# ISL6236A.net
KiCad netlist of a schematic drawn in Altium Designer
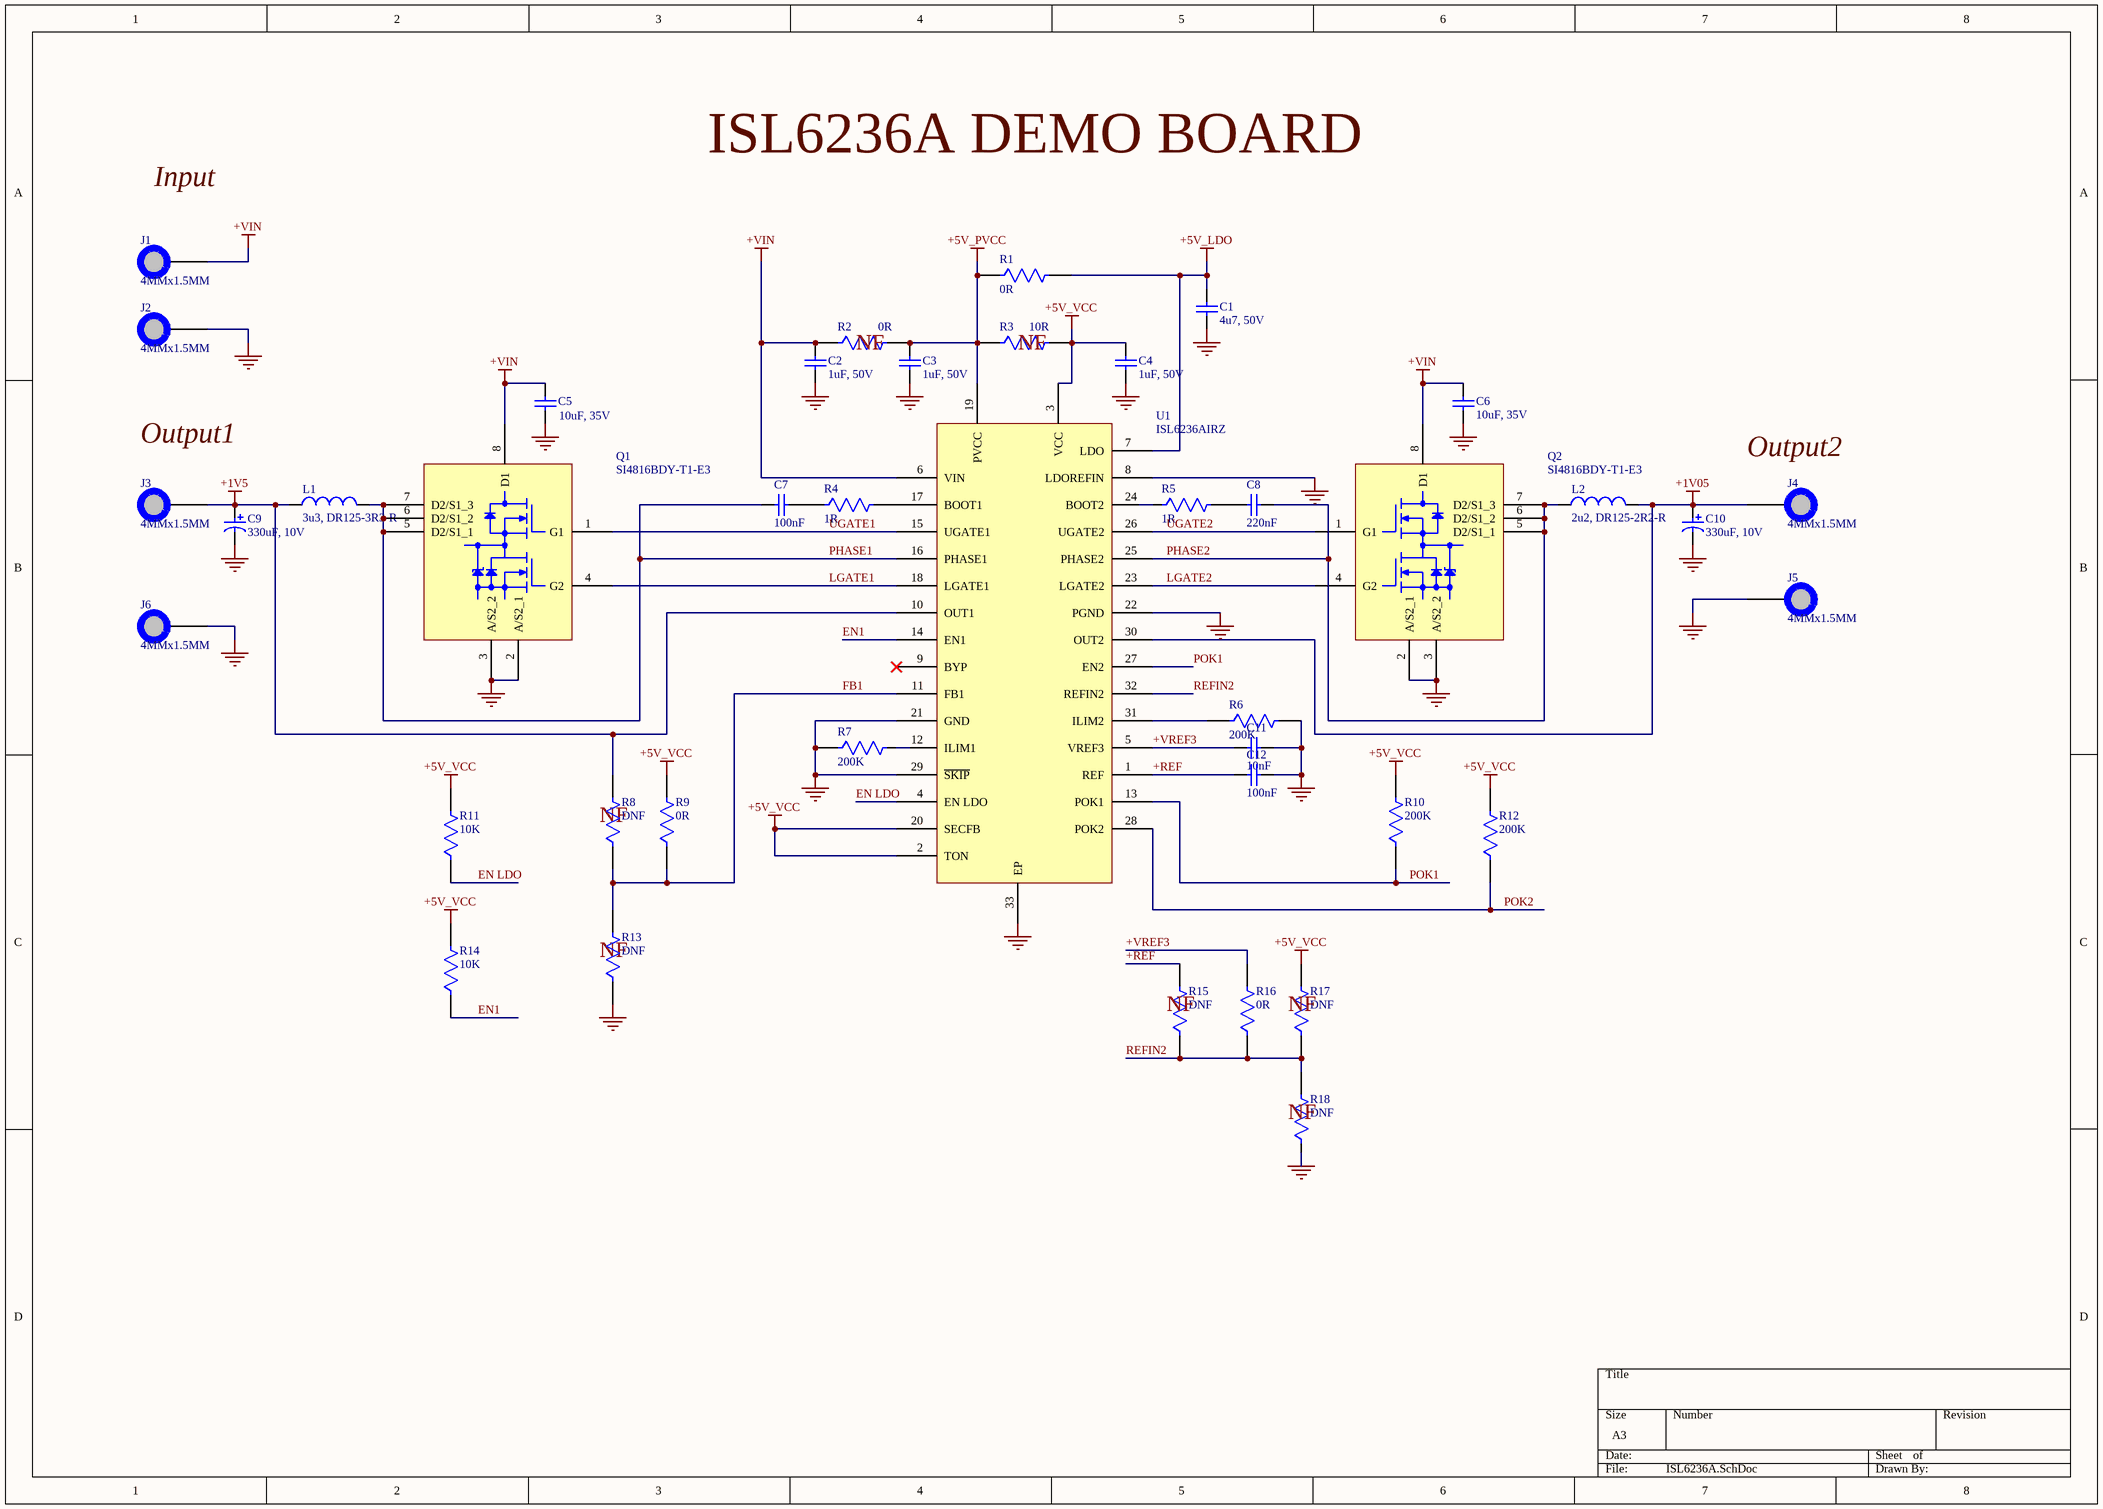
[diagram p0: ISL6236A.SchDoc]

(export (version "E")
  (design (tool "Eeschema 10.0.6"))
  (components
    (comp (ref "C1")
      (value "4u7, 50V")
      (footprint "C1206")
      (description "C Series 1206 4.7 uF 50 V ±10 % Tolerance X5R SMT Multilayer Ceramic Capacitor")
      (fields
        (field (name "MANUFACTURER") "TDK")
        (field (name "MANUFACTURER PART NUMBER") "C3216X5R1H475K160AB")
      )
      (libsource (lib "ISL6236A") (part "C3216X5R1H475K160AB"))
    )
    (comp (ref "C2")
      (value "1uF, 50V")
      (footprint "C0805")
      (description "0805 C 1uF Ceramic Multilayer Capacitor; 50 V; +125degC; X7R Dielectric; +/-10%")
      (fields (field (name "MANUFACTURER") "KEMET") (field (name "TOLERANCE") "10%"))
      (libsource (lib "ISL6236A") (part "C0805C105K5RACTU"))
    )
    (comp (ref "C3")
      (value "1uF, 50V")
      (footprint "C0805")
      (description "0805 C 1uF Ceramic Multilayer Capacitor; 50 V; +125degC; X7R Dielectric; +/-10%")
      (fields (field (name "MANUFACTURER") "KEMET") (field (name "TOLERANCE") "10%"))
      (libsource (lib "ISL6236A") (part "C0805C105K5RACTU"))
    )
    (comp (ref "C4")
      (value "1uF, 50V")
      (footprint "C0805")
      (description "0805 C 1uF Ceramic Multilayer Capacitor; 50 V; +125degC; X7R Dielectric; +/-10%")
      (fields (field (name "MANUFACTURER") "KEMET") (field (name "TOLERANCE") "10%"))
      (libsource (lib "ISL6236A") (part "C0805C105K5RACTU"))
    )
    (comp (ref "C5")
      (value "10uF, 35V")
      (footprint "C1210")
      (fields
        (field (name "MANUFACTURER") "KEMET")
        (field (name "MANUFACTURER PART NUMBER") "C1210C106K6PACTU")
        (field (name "VOLTAGE") "35V")
      )
      (libsource (lib "ISL6236A") (part "C1210C106K6PACTU"))
    )
    (comp (ref "C6")
      (value "10uF, 35V")
      (footprint "C1210")
      (fields
        (field (name "MANUFACTURER") "KEMET")
        (field (name "MANUFACTURER PART NUMBER") "C1210C106K6PACTU")
        (field (name "VOLTAGE") "35V")
      )
      (libsource (lib "ISL6236A") (part "C1210C106K6PACTU"))
    )
    (comp (ref "C7")
      (value "100nF")
      (footprint "C0805")
      (description "Cap Ceramic 0.1uF 50V X7R 10% SMD 2.0 x 1.2 mm 125 C Paper T/R")
      (fields
        (field (name "MANUFACTURER") "KEMET")
        (field (name "MANUFACTURER PART NUMBER") "C0805C104K5RACTU")
      )
      (libsource (lib "ISL6236A") (part "C0805C104K5RACTU"))
    )
    (comp (ref "C8")
      (value "220nF")
      (footprint "C0805")
      (description "CAP CER 0.22UF 50V X7R 0805")
      (fields
        (field (name "MANUFACTURER") "KEMET")
        (field (name "MANUFACTURER PART NUMBER") "C0805C224K5RACTU")
      )
      (libsource (lib "ISL6236A") (part "C0805C224K5RACTU"))
    )
    (comp (ref "C9")
      (value "330uF, 10V")
      (footprint "7343-43")
      (description "Cap Tant Organic 330uF 10VDC X CASE 20% (7.3 X 4.3 X 4mm) SMD 7343-43 0.004 Ohm 125C T/R")
      (fields
        (field (name "MANUFACTURER") "KEMET")
        (field (name "MANUFACTURER PART NUMBER") "T530X337M010ATE004")
      )
      (libsource (lib "ISL6236A") (part "T530X337M010ATE004"))
    )
    (comp (ref "C10")
      (value "330uF, 10V")
      (footprint "7343-43")
      (description "Cap Tant Organic 330uF 10VDC X CASE 20% (7.3 X 4.3 X 4mm) SMD 7343-43 0.004 Ohm 125C T/R")
      (fields
        (field (name "MANUFACTURER") "KEMET")
        (field (name "MANUFACTURER PART NUMBER") "T530X337M010ATE004")
      )
      (libsource (lib "ISL6236A") (part "T530X337M010ATE004"))
    )
    (comp (ref "C11")
      (value "10nF")
      (footprint "C0805")
      (fields
        (field (name "MANUFACTURER") "KEMET")
        (field (name "MANUFACTURER PART NUMBER") "C0805F103K5RACTU")
        (field (name "TOLERANCE") "10%")
      )
      (libsource (lib "ISL6236A") (part "C0805F103K5RACTU"))
    )
    (comp (ref "C12")
      (value "100nF")
      (footprint "C0805")
      (description "Cap Ceramic 0.1uF 50V X7R 10% SMD 2.0 x 1.2 mm 125 C Paper T/R")
      (fields
        (field (name "MANUFACTURER") "KEMET")
        (field (name "MANUFACTURER PART NUMBER") "C0805C104K5RACTU")
      )
      (libsource (lib "ISL6236A") (part "C0805C104K5RACTU"))
    )
    (comp (ref "J1")
      (value "4MMx1.5MM")
      (footprint "PAD_WITH_HOLE_4MMx1MM5")
      (description "Pad with a hole 4mm x 1.5mm")
      (libsource (lib "ISL6236A") (part "PAD_WITH_HOLE_4MMx1MM5"))
    )
    (comp (ref "J2")
      (value "4MMx1.5MM")
      (footprint "PAD_WITH_HOLE_4MMx1MM5")
      (description "Pad with a hole 4mm x 1.5mm")
      (libsource (lib "ISL6236A") (part "PAD_WITH_HOLE_4MMx1MM5"))
    )
    (comp (ref "J3")
      (value "4MMx1.5MM")
      (footprint "PAD_WITH_HOLE_4MMx1MM5")
      (description "Pad with a hole 4mm x 1.5mm")
      (libsource (lib "ISL6236A") (part "PAD_WITH_HOLE_4MMx1MM5"))
    )
    (comp (ref "J4")
      (value "4MMx1.5MM")
      (footprint "PAD_WITH_HOLE_4MMx1MM5")
      (description "Pad with a hole 4mm x 1.5mm")
      (libsource (lib "ISL6236A") (part "PAD_WITH_HOLE_4MMx1MM5"))
    )
    (comp (ref "J5")
      (value "4MMx1.5MM")
      (footprint "PAD_WITH_HOLE_4MMx1MM5")
      (description "Pad with a hole 4mm x 1.5mm")
      (libsource (lib "ISL6236A") (part "PAD_WITH_HOLE_4MMx1MM5"))
    )
    (comp (ref "J6")
      (value "4MMx1.5MM")
      (footprint "PAD_WITH_HOLE_4MMx1MM5")
      (description "Pad with a hole 4mm x 1.5mm")
      (libsource (lib "ISL6236A") (part "PAD_WITH_HOLE_4MMx1MM5"))
    )
    (comp (ref "L1")
      (value "3u3, DR125-3R3-R")
      (footprint "DR125")
      (description "General Purpose Inductor, 3.3uH, 20%, 1 Element, Ferrite-Core, SMD, 4949")
      (fields
        (field (name "MANUFACTURER") "Eaton Cooper")
        (field (name "MANUFACTURER PART NUMBER") "DR125-3R3-R")
      )
      (libsource (lib "ISL6236A") (part "DR125-3R3-R"))
    )
    (comp (ref "L2")
      (value "2u2, DR125-2R2-R")
      (footprint "DR125")
      (description "FIXED IND 2.2UH 10.9A 4.5 MOHM")
      (fields
        (field (name "MANUFACTURER") "Eaton Cooper")
        (field (name "MANUFACTURER PART NUMBER") "DR125-2R2-R")
      )
      (libsource (lib "ISL6236A") (part "DR125-2R2-R"))
    )
    (comp (ref "Q1")
      (value "SI4816BDY-T1-E3")
      (footprint "SO-8")
      (fields (field (name "MANUFACTURER") "Vishay Siliconix"))
      (libsource (lib "") (part "SI4816BDY-T1-E3_1"))
    )
    (comp (ref "Q2")
      (value "SI4816BDY-T1-E3")
      (footprint "SO-8")
      (fields (field (name "MANUFACTURER") "Vishay Siliconix"))
      (libsource (lib "ISL6236A") (part "SI4816BDY-T1-E3"))
    )
    (comp (ref "R1")
      (value "0R")
      (footprint "R0805")
      (description "Fixed Resistor, Metal Glaze/thick Film, 0.125W, 0ohm, Surface Mount, 0805")
      (fields
        (field (name "MANUFACTURER") "Yageo")
        (field (name "MANUFACTURER PART NUMBER") "AC0805JR-070RL")
      )
      (libsource (lib "ISL6236A") (part "AC0805JR-070RL"))
    )
    (comp (ref "R2")
      (value "0R")
      (footprint "R0805")
      (description "Fixed Resistor, Metal Glaze/thick Film, 0.125W, 0ohm, Surface Mount, 0805")
      (fields
        (field (name "MANUFACTURER") "Yageo")
        (field (name "MANUFACTURER PART NUMBER") "AC0805JR-070RL")
      )
      (libsource (lib "ISL6236A") (part "AC0805JR-070RL"))
    )
    (comp (ref "R3")
      (value "10R")
      (footprint "R0805")
      (description "Res Thick Film 0805 10 Ohm 1% 0.125W(1/8W) ±200ppm/C Pad SMD Automotive T/R")
      (fields
        (field (name "MANUFACTURER") "Yageo")
        (field (name "MANUFACTURER PART NUMBER") "AC0805FR-0710RL")
      )
      (libsource (lib "ISL6236A") (part "AC0805FR-0710RL"))
    )
    (comp (ref "R4")
      (value "1R")
      (footprint "R0805")
      (description "Res Thick Film 0805 1 Ohm 1% 0.125W(1/8W) ±200ppm/C Pad SMD Automotive T/R")
      (fields
        (field (name "MANUFACTURER") "Yageo")
        (field (name "MANUFACTURER PART NUMBER") "AC0805FR-071RL")
      )
      (libsource (lib "ISL6236A") (part "AC0805FR-071RL"))
    )
    (comp (ref "R5")
      (value "1R")
      (footprint "R0805")
      (description "Res Thick Film 0805 1 Ohm 1% 0.125W(1/8W) ±200ppm/C Pad SMD Automotive T/R")
      (fields
        (field (name "MANUFACTURER") "Yageo")
        (field (name "MANUFACTURER PART NUMBER") "AC0805FR-071RL")
      )
      (libsource (lib "ISL6236A") (part "AC0805FR-071RL"))
    )
    (comp (ref "R6")
      (value "200K")
      (footprint "R0805")
      (description "Res Thick Film 0805 200K Ohm 1% 0.125W(1/8W) ±100ppm/C Epoxy Pad SMD Automotive T/R")
      (fields
        (field (name "MANUFACTURER") "Yageo")
        (field (name "MANUFACTURER PART NUMBER") "AC0805FR-07200KL")
      )
      (libsource (lib "ISL6236A") (part "AC0805FR-07200KL"))
    )
    (comp (ref "R7")
      (value "200K")
      (footprint "R0805")
      (description "Res Thick Film 0805 200K Ohm 1% 0.125W(1/8W) ±100ppm/C Epoxy Pad SMD Automotive T/R")
      (fields
        (field (name "MANUFACTURER") "Yageo")
        (field (name "MANUFACTURER PART NUMBER") "AC0805FR-07200KL")
      )
      (libsource (lib "ISL6236A") (part "AC0805FR-07200KL"))
    )
    (comp (ref "R8") (value "DNF") (footprint "R0805") (libsource (lib "ISL6236A") (part "RES")))
    (comp (ref "R9")
      (value "0R")
      (footprint "R0805")
      (description "Fixed Resistor, Metal Glaze/thick Film, 0.125W, 0ohm, Surface Mount, 0805")
      (fields
        (field (name "MANUFACTURER") "Yageo")
        (field (name "MANUFACTURER PART NUMBER") "AC0805JR-070RL")
      )
      (libsource (lib "ISL6236A") (part "AC0805JR-070RL"))
    )
    (comp (ref "R10")
      (value "200K")
      (footprint "R0805")
      (description "Res Thick Film 0805 200K Ohm 1% 0.125W(1/8W) ±100ppm/C Epoxy Pad SMD Automotive T/R")
      (fields
        (field (name "MANUFACTURER") "Yageo")
        (field (name "MANUFACTURER PART NUMBER") "AC0805FR-07200KL")
      )
      (libsource (lib "ISL6236A") (part "AC0805FR-07200KL"))
    )
    (comp (ref "R11")
      (value "10K")
      (footprint "R0805")
      (description "Res Thick Film 0805 10K Ohm 1% 0.125W(1/8W) ±100ppm/C Pad SMD Automotive T/R")
      (fields
        (field (name "MANUFACTURER") "Yageo")
        (field (name "MANUFACTURER PART NUMBER") "AC0805FR-0710KL")
      )
      (libsource (lib "ISL6236A") (part "AC0805FR-0710KL"))
    )
    (comp (ref "R12")
      (value "200K")
      (footprint "R0805")
      (description "Res Thick Film 0805 200K Ohm 1% 0.125W(1/8W) ±100ppm/C Epoxy Pad SMD Automotive T/R")
      (fields
        (field (name "MANUFACTURER") "Yageo")
        (field (name "MANUFACTURER PART NUMBER") "AC0805FR-07200KL")
      )
      (libsource (lib "ISL6236A") (part "AC0805FR-07200KL"))
    )
    (comp (ref "R13") (value "DNF") (footprint "R0805") (libsource (lib "ISL6236A") (part "RES")))
    (comp (ref "R14")
      (value "10K")
      (footprint "R0805")
      (description "Res Thick Film 0805 10K Ohm 1% 0.125W(1/8W) ±100ppm/C Pad SMD Automotive T/R")
      (fields
        (field (name "MANUFACTURER") "Yageo")
        (field (name "MANUFACTURER PART NUMBER") "AC0805FR-0710KL")
      )
      (libsource (lib "ISL6236A") (part "AC0805FR-0710KL"))
    )
    (comp (ref "R15") (value "DNF") (footprint "R0805") (libsource (lib "ISL6236A") (part "RES")))
    (comp (ref "R16")
      (value "0R")
      (footprint "R0805")
      (description "Fixed Resistor, Metal Glaze/thick Film, 0.125W, 0ohm, Surface Mount, 0805")
      (fields
        (field (name "MANUFACTURER") "Yageo")
        (field (name "MANUFACTURER PART NUMBER") "AC0805JR-070RL")
      )
      (libsource (lib "ISL6236A") (part "AC0805JR-070RL"))
    )
    (comp (ref "R17") (value "DNF") (footprint "R0805") (libsource (lib "ISL6236A") (part "RES")))
    (comp (ref "R18") (value "DNF") (footprint "R0805") (libsource (lib "ISL6236A") (part "RES")))
    (comp (ref "U1")
      (value "ISL6236AIRZ")
      (footprint "L32.5x5B")
      (description "IC MAIN PWR CTRLR QUAD 32-QFN")
      (fields (field (name "MANUFACTURER") "Renesas"))
      (libsource (lib "ISL6236A") (part "ISL6236AIRZ"))
    )
  )
  (nets
    (net (code "1") (name "+1V5") (class "Default")
      (node (ref "C9") (pin "1") (pinfunction "1_1") (pintype "passive"))
      (node (ref "J3") (pin "1") (pinfunction "1_1") (pintype "passive"))
      (node (ref "L1") (pin "1") (pinfunction "1_1") (pintype "passive"))
      (node (ref "R8") (pin "2") (pinfunction "2_2") (pintype "passive"))
      (node (ref "U1") (pin "10") (pinfunction "OUT1_10") (pintype "passive"))
    )
    (net (code "2") (name "+1V05") (class "Default")
      (node (ref "C10") (pin "1") (pinfunction "1_1") (pintype "passive"))
      (node (ref "J4") (pin "1") (pinfunction "1_1") (pintype "passive"))
      (node (ref "L2") (pin "2") (pinfunction "2_2") (pintype "passive"))
      (node (ref "U1") (pin "30") (pinfunction "OUT2_30") (pintype "passive"))
    )
    (net (code "3") (name "+5V_LDO") (class "Default")
      (node (ref "C1") (pin "2") (pinfunction "2_2") (pintype "passive"))
      (node (ref "R1") (pin "2") (pinfunction "2_2") (pintype "passive"))
      (node (ref "U1") (pin "7") (pinfunction "LDO_7") (pintype "passive"))
    )
    (net (code "4") (name "+5V_PVCC") (class "Default")
      (node (ref "C3") (pin "2") (pinfunction "2_2") (pintype "passive"))
      (node (ref "R1") (pin "1") (pinfunction "1_1") (pintype "passive"))
      (node (ref "R2") (pin "2") (pinfunction "2_2") (pintype "passive"))
      (node (ref "R3") (pin "1") (pinfunction "1_1") (pintype "passive"))
      (node (ref "U1") (pin "19") (pinfunction "PVCC_19") (pintype "passive"))
    )
    (net (code "5") (name "+5V_VCC") (class "Default")
      (node (ref "C4") (pin "2") (pinfunction "2_2") (pintype "passive"))
      (node (ref "R10") (pin "2") (pinfunction "2_2") (pintype "passive"))
      (node (ref "R11") (pin "2") (pinfunction "2_2") (pintype "passive"))
      (node (ref "R12") (pin "2") (pinfunction "2_2") (pintype "passive"))
      (node (ref "R14") (pin "2") (pinfunction "2_2") (pintype "passive"))
      (node (ref "R17") (pin "2") (pinfunction "2_2") (pintype "passive"))
      (node (ref "R3") (pin "2") (pinfunction "2_2") (pintype "passive"))
      (node (ref "R9") (pin "2") (pinfunction "2_2") (pintype "passive"))
      (node (ref "U1") (pin "2") (pinfunction "TON_2") (pintype "passive"))
      (node (ref "U1") (pin "20") (pinfunction "SECFB_20") (pintype "passive"))
      (node (ref "U1") (pin "3") (pinfunction "VCC_3") (pintype "passive"))
    )
    (net (code "6") (name "+VIN") (class "Default")
      (node (ref "C2") (pin "2") (pinfunction "2_2") (pintype "passive"))
      (node (ref "C5") (pin "2") (pinfunction "2_2") (pintype "passive"))
      (node (ref "C6") (pin "2") (pinfunction "2_2") (pintype "passive"))
      (node (ref "J1") (pin "1") (pinfunction "1_1") (pintype "passive"))
      (node (ref "Q1") (pin "8") (pinfunction "D1_8") (pintype "passive"))
      (node (ref "Q2") (pin "8") (pinfunction "D1_8") (pintype "passive"))
      (node (ref "R2") (pin "1") (pinfunction "1_1") (pintype "passive"))
      (node (ref "U1") (pin "6") (pinfunction "VIN_6") (pintype "passive"))
    )
    (net (code "7") (name "/+REF") (class "Default")
      (node (ref "C12") (pin "1") (pinfunction "1_1") (pintype "passive"))
      (node (ref "R15") (pin "2") (pinfunction "2_2") (pintype "passive"))
      (node (ref "U1") (pin "1") (pinfunction "REF_1") (pintype "passive"))
    )
    (net (code "8") (name "/+VREF3") (class "Default")
      (node (ref "C11") (pin "1") (pinfunction "1_1") (pintype "passive"))
      (node (ref "R16") (pin "2") (pinfunction "2_2") (pintype "passive"))
      (node (ref "U1") (pin "5") (pinfunction "VREF3_5") (pintype "passive"))
    )
    (net (code "9") (name "/EN LDO") (class "Default")
      (node (ref "R11") (pin "1") (pinfunction "1_1") (pintype "passive"))
      (node (ref "U1") (pin "4") (pinfunction "EN_LDO_4") (pintype "passive"))
    )
    (net (code "10") (name "/EN1") (class "Default")
      (node (ref "R14") (pin "1") (pinfunction "1_1") (pintype "passive"))
      (node (ref "U1") (pin "14") (pinfunction "EN1_14") (pintype "passive"))
    )
    (net (code "11") (name "/FB1") (class "Default")
      (node (ref "R13") (pin "2") (pinfunction "2_2") (pintype "passive"))
      (node (ref "R8") (pin "1") (pinfunction "1_1") (pintype "passive"))
      (node (ref "R9") (pin "1") (pinfunction "1_1") (pintype "passive"))
      (node (ref "U1") (pin "11") (pinfunction "FB1_11") (pintype "passive"))
    )
    (net (code "12") (name "/LGATE1") (class "Default")
      (node (ref "Q1") (pin "4") (pinfunction "G2_4") (pintype "passive"))
      (node (ref "U1") (pin "18") (pinfunction "LGATE1_18") (pintype "passive"))
    )
    (net (code "13") (name "/LGATE2") (class "Default")
      (node (ref "Q2") (pin "4") (pinfunction "G2_4") (pintype "passive"))
      (node (ref "U1") (pin "23") (pinfunction "LGATE2_23") (pintype "passive"))
    )
    (net (code "14") (name "/PHASE1") (class "Default")
      (node (ref "C7") (pin "1") (pinfunction "1_1") (pintype "passive"))
      (node (ref "L1") (pin "2") (pinfunction "2_2") (pintype "passive"))
      (node (ref "Q1") (pin "5") (pinfunction "D2/S1_1_5") (pintype "passive"))
      (node (ref "Q1") (pin "6") (pinfunction "D2/S1_2_6") (pintype "passive"))
      (node (ref "Q1") (pin "7") (pinfunction "D2/S1_3_7") (pintype "passive"))
      (node (ref "U1") (pin "16") (pinfunction "PHASE1_16") (pintype "passive"))
    )
    (net (code "15") (name "/PHASE2") (class "Default")
      (node (ref "C8") (pin "2") (pinfunction "2_2") (pintype "passive"))
      (node (ref "L2") (pin "1") (pinfunction "1_1") (pintype "passive"))
      (node (ref "Q2") (pin "5") (pinfunction "D2/S1_1_5") (pintype "passive"))
      (node (ref "Q2") (pin "6") (pinfunction "D2/S1_2_6") (pintype "passive"))
      (node (ref "Q2") (pin "7") (pinfunction "D2/S1_3_7") (pintype "passive"))
      (node (ref "U1") (pin "25") (pinfunction "PHASE2_25") (pintype "passive"))
    )
    (net (code "16") (name "/POK1") (class "Default")
      (node (ref "R10") (pin "1") (pinfunction "1_1") (pintype "passive"))
      (node (ref "U1") (pin "13") (pinfunction "POK1_13") (pintype "passive"))
      (node (ref "U1") (pin "27") (pinfunction "EN2_27") (pintype "passive"))
    )
    (net (code "17") (name "/POK2") (class "Default")
      (node (ref "R12") (pin "1") (pinfunction "1_1") (pintype "passive"))
      (node (ref "U1") (pin "28") (pinfunction "POK2_28") (pintype "passive"))
    )
    (net (code "18") (name "/REFIN2") (class "Default")
      (node (ref "R15") (pin "1") (pinfunction "1_1") (pintype "passive"))
      (node (ref "R16") (pin "1") (pinfunction "1_1") (pintype "passive"))
      (node (ref "R17") (pin "1") (pinfunction "1_1") (pintype "passive"))
      (node (ref "R18") (pin "2") (pinfunction "2_2") (pintype "passive"))
      (node (ref "U1") (pin "32") (pinfunction "REFIN2_32") (pintype "passive"))
    )
    (net (code "19") (name "/UGATE1") (class "Default")
      (node (ref "Q1") (pin "1") (pinfunction "G1_1") (pintype "passive"))
      (node (ref "U1") (pin "15") (pinfunction "UGATE1_15") (pintype "passive"))
    )
    (net (code "20") (name "/UGATE2") (class "Default")
      (node (ref "Q2") (pin "1") (pinfunction "G1_1") (pintype "passive"))
      (node (ref "U1") (pin "26") (pinfunction "UGATE2_26") (pintype "passive"))
    )
    (net (code "21") (name "GND") (class "Default")
      (node (ref "C1") (pin "1") (pinfunction "1_1") (pintype "passive"))
      (node (ref "C10") (pin "2") (pinfunction "2_2") (pintype "passive"))
      (node (ref "C11") (pin "2") (pinfunction "2_2") (pintype "passive"))
      (node (ref "C12") (pin "2") (pinfunction "2_2") (pintype "passive"))
      (node (ref "C2") (pin "1") (pinfunction "1_1") (pintype "passive"))
      (node (ref "C3") (pin "1") (pinfunction "1_1") (pintype "passive"))
      (node (ref "C4") (pin "1") (pinfunction "1_1") (pintype "passive"))
      (node (ref "C5") (pin "1") (pinfunction "1_1") (pintype "passive"))
      (node (ref "C6") (pin "1") (pinfunction "1_1") (pintype "passive"))
      (node (ref "C9") (pin "2") (pinfunction "2_2") (pintype "passive"))
      (node (ref "J2") (pin "1") (pinfunction "1_1") (pintype "passive"))
      (node (ref "J5") (pin "1") (pinfunction "1_1") (pintype "passive"))
      (node (ref "J6") (pin "1") (pinfunction "1_1") (pintype "passive"))
      (node (ref "Q1") (pin "2") (pinfunction "A/S2_1_2") (pintype "passive"))
      (node (ref "Q1") (pin "3") (pinfunction "A/S2_2_3") (pintype "passive"))
      (node (ref "Q2") (pin "2") (pinfunction "A/S2_1_2") (pintype "passive"))
      (node (ref "Q2") (pin "3") (pinfunction "A/S2_2_3") (pintype "passive"))
      (node (ref "R13") (pin "1") (pinfunction "1_1") (pintype "passive"))
      (node (ref "R18") (pin "1") (pinfunction "1_1") (pintype "passive"))
      (node (ref "R6") (pin "2") (pinfunction "2_2") (pintype "passive"))
      (node (ref "R7") (pin "1") (pinfunction "1_1") (pintype "passive"))
      (node (ref "U1") (pin "21") (pinfunction "GND_21") (pintype "passive"))
      (node (ref "U1") (pin "22") (pinfunction "PGND_22") (pintype "passive"))
      (node (ref "U1") (pin "29") (pinfunction "~{SKIP}_29") (pintype "passive"))
      (node (ref "U1") (pin "33") (pinfunction "EP_33") (pintype "passive"))
      (node (ref "U1") (pin "8") (pinfunction "LDOREFIN_8") (pintype "passive"))
    )
    (net (code "22") (name "Net-(C7-Pad2)") (class "Default")
      (node (ref "C7") (pin "2") (pinfunction "2_2") (pintype "passive"))
      (node (ref "R4") (pin "1") (pinfunction "1_1") (pintype "passive"))
    )
    (net (code "23") (name "Net-(C8-Pad1)") (class "Default")
      (node (ref "C8") (pin "1") (pinfunction "1_1") (pintype "passive"))
      (node (ref "R5") (pin "2") (pinfunction "2_2") (pintype "passive"))
    )
    (net (code "24") (name "Net-(U1-BOOT1)") (class "Default")
      (node (ref "R4") (pin "2") (pinfunction "2_2") (pintype "passive"))
      (node (ref "U1") (pin "17") (pinfunction "BOOT1_17") (pintype "passive"))
    )
    (net (code "25") (name "Net-(U1-BOOT2)") (class "Default")
      (node (ref "R5") (pin "1") (pinfunction "1_1") (pintype "passive"))
      (node (ref "U1") (pin "24") (pinfunction "BOOT2_24") (pintype "passive"))
    )
    (net (code "26") (name "Net-(U1-ILIM1)") (class "Default")
      (node (ref "R7") (pin "2") (pinfunction "2_2") (pintype "passive"))
      (node (ref "U1") (pin "12") (pinfunction "ILIM1_12") (pintype "passive"))
    )
    (net (code "27") (name "Net-(U1-ILIM2)") (class "Default")
      (node (ref "R6") (pin "1") (pinfunction "1_1") (pintype "passive"))
      (node (ref "U1") (pin "31") (pinfunction "ILIM2_31") (pintype "passive"))
    )
    (net (code "28") (name "unconnected-(U1-BYP-Pad9)") (class "Default")
      (node (ref "U1") (pin "9") (pinfunction "BYP_9") (pintype "passive+no_connect"))
    )
  )
)
